# attiny85.net
KiCad netlist of a schematic drawn in EAGLE
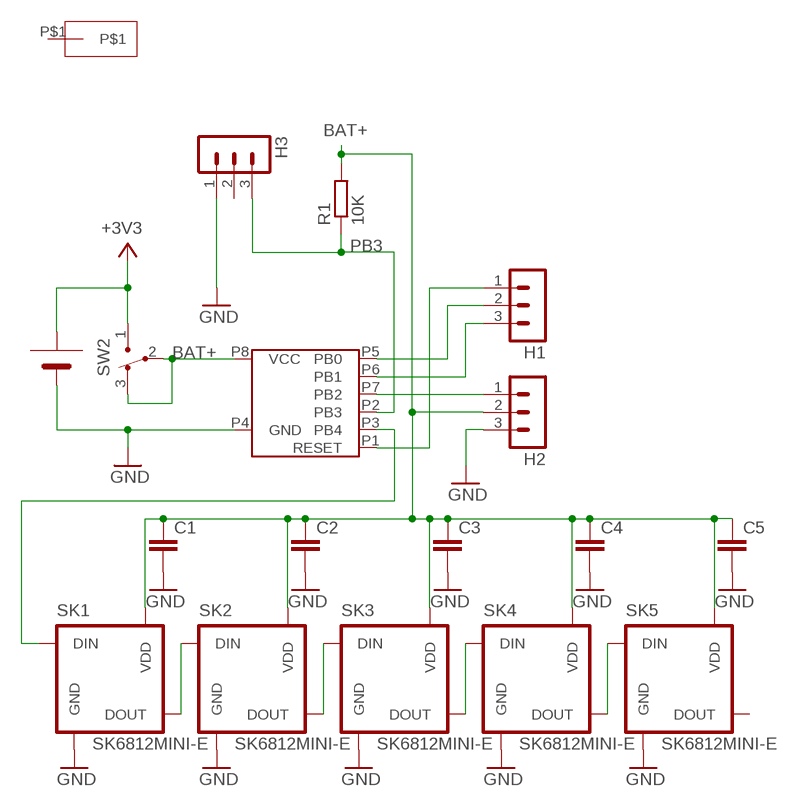
[diagram p0: schematic, sheet 1]

(export (version "E")
  (design (tool "Eeschema 10.0.6"))
  (components
    (comp (ref "ATTINY85-1")
      (value "ATTINY85")
      (footprint "eagle-import:ATTINY85-20SUR")
      (libsource (lib "eagle-import") (part "ATTINY85SOP8"))
    )
    (comp (ref "BAT1")
      (value "BAT-CR2032B")
      (footprint "eagle-import:BAT-CR2032-2")
      (libsource (lib "eagle-import") (part "BAT-CR2032B"))
    )
    (comp (ref "C1")
      (value "C-EUC2012")
      (footprint "eagle-import:C2012")
      (libsource (lib "eagle-import") (part "C-EUC2012"))
    )
    (comp (ref "C2")
      (value "C-EUC2012")
      (footprint "eagle-import:C2012")
      (libsource (lib "eagle-import") (part "C-EUC2012"))
    )
    (comp (ref "C3")
      (value "C-EUC2012")
      (footprint "eagle-import:C2012")
      (libsource (lib "eagle-import") (part "C-EUC2012"))
    )
    (comp (ref "C4")
      (value "C-EUC2012")
      (footprint "eagle-import:C2012")
      (libsource (lib "eagle-import") (part "C-EUC2012"))
    )
    (comp (ref "C5")
      (value "C-EUC2012")
      (footprint "eagle-import:C2012")
      (libsource (lib "eagle-import") (part "C-EUC2012"))
    )
    (comp (ref "H1")
      (value "PINHEAD-MA03-1SMD")
      (footprint "eagle-import:PINHEAD-MA03-2")
      (libsource (lib "eagle-import") (part "PINHEAD-MA03-1SMD"))
    )
    (comp (ref "H2")
      (value "PINHEAD-MA03-1SMD")
      (footprint "eagle-import:PINHEAD-MA03-2")
      (libsource (lib "eagle-import") (part "PINHEAD-MA03-1SMD"))
    )
    (comp (ref "H3")
      (value "PINHEAD-MA03-1")
      (footprint "eagle-import:PINHEAD-MA03-1")
      (libsource (lib "eagle-import") (part "PINHEAD-MA03-1"))
    )
    (comp (ref "PAD33")
      (value "PAD_10X3")
      (footprint "eagle-import:PAD-10X3")
      (libsource (lib "eagle-import") (part "PAD_10X3"))
    )
    (comp (ref "R1")
      (value "10K")
      (footprint "eagle-import:M3216")
      (libsource (lib "eagle-import") (part "R-EU_M3216"))
    )
    (comp (ref "SK1")
      (value "SK6812MINI-E")
      (footprint "eagle-import:SK6812MINI-E")
      (libsource (lib "eagle-import") (part "SK6812MINI-E"))
    )
    (comp (ref "SK2")
      (value "SK6812MINI-E")
      (footprint "eagle-import:SK6812MINI-E")
      (libsource (lib "eagle-import") (part "SK6812MINI-E"))
    )
    (comp (ref "SK3")
      (value "SK6812MINI-E")
      (footprint "eagle-import:SK6812MINI-E")
      (libsource (lib "eagle-import") (part "SK6812MINI-E"))
    )
    (comp (ref "SK4")
      (value "SK6812MINI-E")
      (footprint "eagle-import:SK6812MINI-E")
      (libsource (lib "eagle-import") (part "SK6812MINI-E"))
    )
    (comp (ref "SK5")
      (value "SK6812MINI-E")
      (footprint "eagle-import:SK6812MINI-E")
      (libsource (lib "eagle-import") (part "SK6812MINI-E"))
    )
    (comp (ref "SW2")
      (value "POWER")
      (footprint "eagle-import:SW3-1")
      (fields (field (name "MF") "HiLetgo"))
      (libsource (lib "eagle-import") (part "SW3-1"))
    )
  )
  (nets
    (net (code "1") (name "+3V3") (class "Default")
      (node (ref "BAT1") (pin "BAT+") (pinfunction "BAT+_BAT+") (pintype "bidirectional"))
      (node (ref "SW2") (pin "1") (pinfunction "1_1") (pintype "passive"))
    )
    (net (code "2") (name "/BAT+") (class "Default")
      (node (ref "ATTINY85-1") (pin "P8") (pinfunction "VCC_P8") (pintype "bidirectional"))
      (node (ref "C1") (pin "1") (pinfunction "1_1") (pintype "passive"))
      (node (ref "C2") (pin "1") (pinfunction "1_1") (pintype "passive"))
      (node (ref "C3") (pin "1") (pinfunction "1_1") (pintype "passive"))
      (node (ref "C4") (pin "1") (pinfunction "1_1") (pintype "passive"))
      (node (ref "C5") (pin "1") (pinfunction "1_1") (pintype "passive"))
      (node (ref "H2") (pin "2") (pinfunction "2_2") (pintype "passive"))
      (node (ref "R1") (pin "2") (pinfunction "2_2") (pintype "passive"))
      (node (ref "SK1") (pin "VDD") (pinfunction "VDD_VDD") (pintype "bidirectional"))
      (node (ref "SK2") (pin "VDD") (pinfunction "VDD_VDD") (pintype "bidirectional"))
      (node (ref "SK3") (pin "VDD") (pinfunction "VDD_VDD") (pintype "bidirectional"))
      (node (ref "SK4") (pin "VDD") (pinfunction "VDD_VDD") (pintype "bidirectional"))
      (node (ref "SK5") (pin "VDD") (pinfunction "VDD_VDD") (pintype "bidirectional"))
      (node (ref "SW2") (pin "2") (pinfunction "2_2") (pintype "passive"))
      (node (ref "SW2") (pin "3") (pinfunction "3_3") (pintype "passive"))
    )
    (net (code "3") (name "/PB3") (class "Default")
      (node (ref "ATTINY85-1") (pin "P2") (pinfunction "PB3_P2") (pintype "bidirectional"))
      (node (ref "H3") (pin "3") (pinfunction "3_3") (pintype "passive"))
      (node (ref "R1") (pin "1") (pinfunction "1_1") (pintype "passive"))
    )
    (net (code "4") (name "GND") (class "Default")
      (node (ref "ATTINY85-1") (pin "P4") (pinfunction "GND_P4") (pintype "bidirectional"))
      (node (ref "BAT1") (pin "BAT-") (pinfunction "P$1_BAT-") (pintype "bidirectional"))
      (node (ref "C1") (pin "2") (pinfunction "2_2") (pintype "passive"))
      (node (ref "C2") (pin "2") (pinfunction "2_2") (pintype "passive"))
      (node (ref "C3") (pin "2") (pinfunction "2_2") (pintype "passive"))
      (node (ref "C4") (pin "2") (pinfunction "2_2") (pintype "passive"))
      (node (ref "C5") (pin "2") (pinfunction "2_2") (pintype "passive"))
      (node (ref "H2") (pin "3") (pinfunction "3_3") (pintype "passive"))
      (node (ref "H3") (pin "1") (pinfunction "1_1") (pintype "passive"))
      (node (ref "SK1") (pin "GND") (pinfunction "GND_GND") (pintype "bidirectional"))
      (node (ref "SK2") (pin "GND") (pinfunction "GND_GND") (pintype "bidirectional"))
      (node (ref "SK3") (pin "GND") (pinfunction "GND_GND") (pintype "bidirectional"))
      (node (ref "SK4") (pin "GND") (pinfunction "GND_GND") (pintype "bidirectional"))
      (node (ref "SK5") (pin "GND") (pinfunction "GND_GND") (pintype "bidirectional"))
    )
    (net (code "5") (name "Net-(ATTINY85-1-PB0)") (class "Default")
      (node (ref "ATTINY85-1") (pin "P5") (pinfunction "PB0_P5") (pintype "bidirectional"))
      (node (ref "H1") (pin "2") (pinfunction "2_2") (pintype "passive"))
    )
    (net (code "6") (name "Net-(ATTINY85-1-PB1)") (class "Default")
      (node (ref "ATTINY85-1") (pin "P6") (pinfunction "PB1_P6") (pintype "bidirectional"))
      (node (ref "H1") (pin "3") (pinfunction "3_3") (pintype "passive"))
    )
    (net (code "7") (name "Net-(ATTINY85-1-PB2)") (class "Default")
      (node (ref "ATTINY85-1") (pin "P7") (pinfunction "PB2_P7") (pintype "bidirectional"))
      (node (ref "H2") (pin "1") (pinfunction "1_1") (pintype "passive"))
    )
    (net (code "8") (name "Net-(ATTINY85-1-PB4)") (class "Default")
      (node (ref "ATTINY85-1") (pin "P3") (pinfunction "PB4_P3") (pintype "bidirectional"))
      (node (ref "SK1") (pin "DIN") (pinfunction "DIN_DIN") (pintype "input"))
    )
    (net (code "9") (name "Net-(ATTINY85-1-RESET)") (class "Default")
      (node (ref "ATTINY85-1") (pin "P1") (pinfunction "RESET_P1") (pintype "bidirectional"))
      (node (ref "H1") (pin "1") (pinfunction "1_1") (pintype "passive"))
    )
    (net (code "10") (name "Net-(SK1-PadDOUT)") (class "Default")
      (node (ref "SK1") (pin "DOUT") (pinfunction "DOUT_DOUT") (pintype "output"))
      (node (ref "SK2") (pin "DIN") (pinfunction "DIN_DIN") (pintype "input"))
    )
    (net (code "11") (name "Net-(SK2-PadDOUT)") (class "Default")
      (node (ref "SK2") (pin "DOUT") (pinfunction "DOUT_DOUT") (pintype "output"))
      (node (ref "SK3") (pin "DIN") (pinfunction "DIN_DIN") (pintype "input"))
    )
    (net (code "12") (name "Net-(SK3-PadDOUT)") (class "Default")
      (node (ref "SK3") (pin "DOUT") (pinfunction "DOUT_DOUT") (pintype "output"))
      (node (ref "SK4") (pin "DIN") (pinfunction "DIN_DIN") (pintype "input"))
    )
    (net (code "13") (name "Net-(SK4-PadDOUT)") (class "Default")
      (node (ref "SK4") (pin "DOUT") (pinfunction "DOUT_DOUT") (pintype "output"))
      (node (ref "SK5") (pin "DIN") (pinfunction "DIN_DIN") (pintype "input"))
    )
    (net (code "14") (name "unconnected-(H3-Pad2)") (class "Default")
      (node (ref "H3") (pin "2") (pinfunction "2_2") (pintype "passive"))
    )
    (net (code "15") (name "unconnected-(PAD33-PadP$1)") (class "Default")
      (node (ref "PAD33") (pin "P$1") (pinfunction "P$1_P$1") (pintype "bidirectional"))
    )
    (net (code "16") (name "unconnected-(SK5-PadDOUT)") (class "Default")
      (node (ref "SK5") (pin "DOUT") (pinfunction "DOUT_DOUT") (pintype "output"))
    )
  )
)
